# OLED_Shield.net
KiCad netlist of a schematic drawn in EAGLE
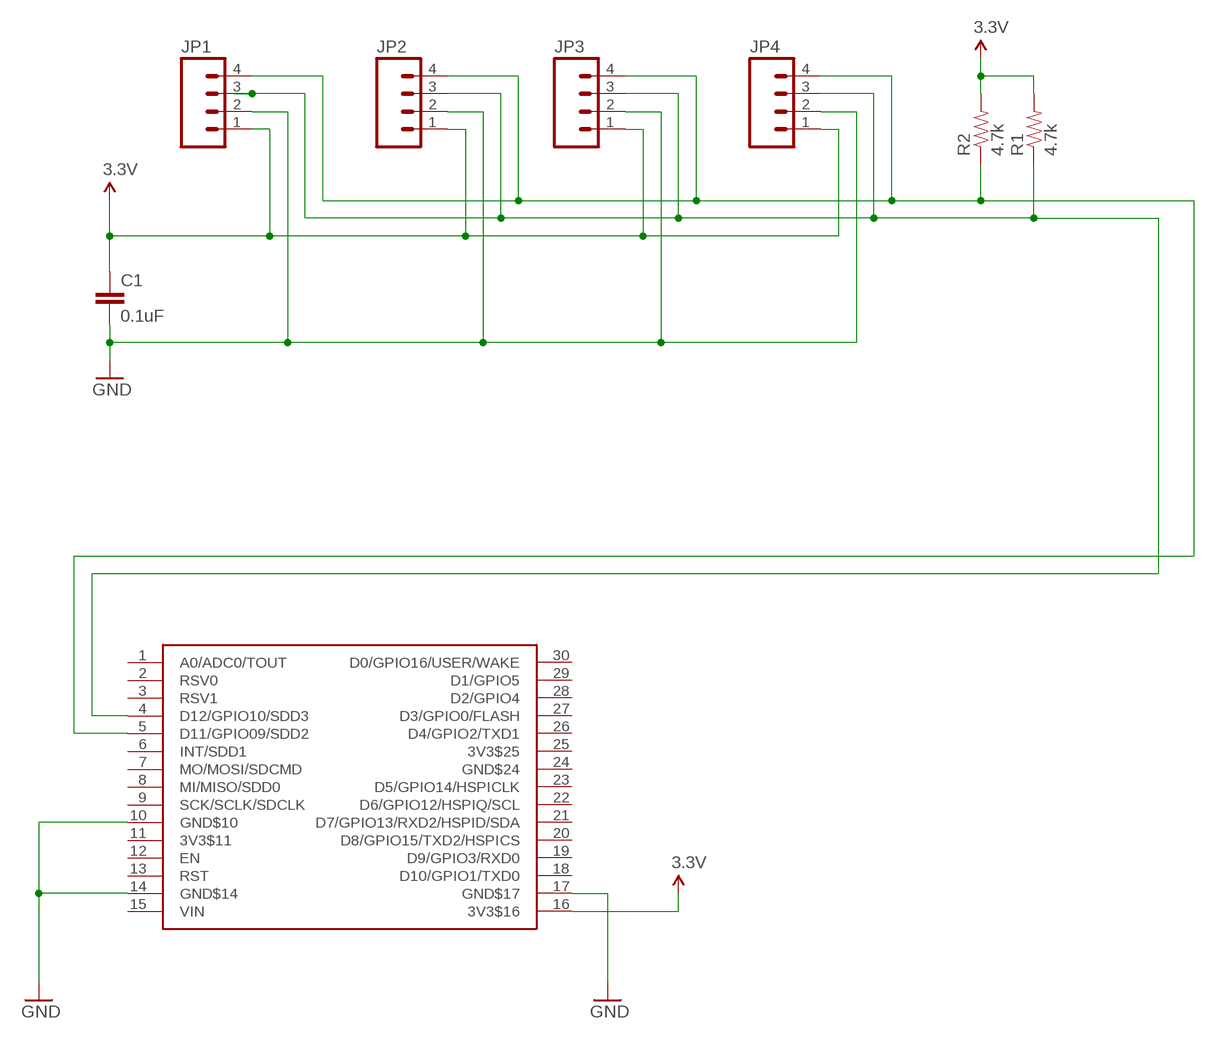
[diagram p0: schematic, sheet 1]

(export (version "E")
  (design (tool "Eeschema 10.0.6"))
  (components
    (comp (ref "C1")
      (value "0.1uF")
      (footprint "eagle-import:0402-CAP")
      (libsource (lib "eagle-import") (part "CAP0402-CAP"))
    )
    (comp (ref "JP1")
      (value "M041X04_NO_SILK")
      (footprint "eagle-import:1X04_NO_SILK")
      (libsource (lib "eagle-import") (part "M041X04_NO_SILK"))
    )
    (comp (ref "JP2")
      (value "M041X04_NO_SILK")
      (footprint "eagle-import:1X04_NO_SILK")
      (libsource (lib "eagle-import") (part "M041X04_NO_SILK"))
    )
    (comp (ref "JP3")
      (value "M041X04_NO_SILK")
      (footprint "eagle-import:1X04_NO_SILK")
      (libsource (lib "eagle-import") (part "M041X04_NO_SILK"))
    )
    (comp (ref "JP4")
      (value "M041X04_NO_SILK")
      (footprint "eagle-import:1X04_NO_SILK")
      (libsource (lib "eagle-import") (part "M041X04_NO_SILK"))
    )
    (comp (ref "R1")
      (value "4.7k")
      (footprint "eagle-import:0402-RES")
      (libsource (lib "eagle-import") (part "RESISTOR0402-RES"))
    )
    (comp (ref "R2")
      (value "4.7k")
      (footprint "eagle-import:0402-RES")
      (libsource (lib "eagle-import") (part "RESISTOR0402-RES"))
    )
    (comp (ref "U$1")
      (value "NERDSHIELD")
      (footprint "eagle-import:NERDUINO_STACK")
      (libsource (lib "eagle-import") (part "NERDSHIELD"))
    )
  )
  (nets
    (net (code "1") (name "3.3V") (class "Default")
      (node (ref "C1") (pin "1") (pinfunction "1_1") (pintype "passive"))
      (node (ref "JP1") (pin "1") (pinfunction "1_1") (pintype "passive"))
      (node (ref "JP2") (pin "1") (pinfunction "1_1") (pintype "passive"))
      (node (ref "JP3") (pin "1") (pinfunction "1_1") (pintype "passive"))
      (node (ref "JP4") (pin "1") (pinfunction "1_1") (pintype "passive"))
      (node (ref "R1") (pin "2") (pinfunction "2_2") (pintype "passive"))
      (node (ref "R2") (pin "2") (pinfunction "2_2") (pintype "passive"))
      (node (ref "U$1") (pin "16") (pinfunction "3V3$16_16") (pintype "bidirectional"))
    )
    (net (code "2") (name "GND") (class "Default")
      (node (ref "C1") (pin "2") (pinfunction "2_2") (pintype "passive"))
      (node (ref "JP1") (pin "2") (pinfunction "2_2") (pintype "passive"))
      (node (ref "JP2") (pin "2") (pinfunction "2_2") (pintype "passive"))
      (node (ref "JP3") (pin "2") (pinfunction "2_2") (pintype "passive"))
      (node (ref "JP4") (pin "2") (pinfunction "2_2") (pintype "passive"))
      (node (ref "U$1") (pin "10") (pinfunction "GND$10_10") (pintype "bidirectional"))
      (node (ref "U$1") (pin "14") (pinfunction "GND$14_14") (pintype "bidirectional"))
      (node (ref "U$1") (pin "17") (pinfunction "GND$17_17") (pintype "bidirectional"))
    )
    (net (code "3") (name "Net-(U$1-D11{slash}GPIO09{slash}SDD2)") (class "Default")
      (node (ref "JP1") (pin "4") (pinfunction "4_4") (pintype "passive"))
      (node (ref "JP2") (pin "4") (pinfunction "4_4") (pintype "passive"))
      (node (ref "JP3") (pin "4") (pinfunction "4_4") (pintype "passive"))
      (node (ref "JP4") (pin "4") (pinfunction "4_4") (pintype "passive"))
      (node (ref "R2") (pin "1") (pinfunction "1_1") (pintype "passive"))
      (node (ref "U$1") (pin "5") (pinfunction "D11/GPIO09/SDD2_5") (pintype "bidirectional"))
    )
    (net (code "4") (name "Net-(U$1-D12{slash}GPIO10{slash}SDD3)") (class "Default")
      (node (ref "JP1") (pin "3") (pinfunction "3_3") (pintype "passive"))
      (node (ref "JP2") (pin "3") (pinfunction "3_3") (pintype "passive"))
      (node (ref "JP3") (pin "3") (pinfunction "3_3") (pintype "passive"))
      (node (ref "JP4") (pin "3") (pinfunction "3_3") (pintype "passive"))
      (node (ref "R1") (pin "1") (pinfunction "1_1") (pintype "passive"))
      (node (ref "U$1") (pin "4") (pinfunction "D12/GPIO10/SDD3_4") (pintype "bidirectional"))
    )
    (net (code "5") (name "unconnected-(U$1-3V3$11-Pad11)") (class "Default")
      (node (ref "U$1") (pin "11") (pinfunction "3V3$11_11") (pintype "bidirectional"))
    )
    (net (code "6") (name "unconnected-(U$1-3V3$25-Pad25)") (class "Default")
      (node (ref "U$1") (pin "25") (pinfunction "3V3$25_25") (pintype "bidirectional"))
    )
    (net (code "7") (name "unconnected-(U$1-A0{slash}ADC0{slash}TOUT-Pad1)") (class "Default")
      (node (ref "U$1") (pin "1") (pinfunction "A0/ADC0/TOUT_1") (pintype "bidirectional"))
    )
    (net (code "8") (name "unconnected-(U$1-D0{slash}GPIO16{slash}USER{slash}WAKE-Pad30)") (class "Default")
      (node (ref "U$1") (pin "30") (pinfunction "D0/GPIO16/USER/WAKE_30") (pintype "bidirectional"))
    )
    (net (code "9") (name "unconnected-(U$1-D1{slash}GPIO5-Pad29)") (class "Default")
      (node (ref "U$1") (pin "29") (pinfunction "D1/GPIO5_29") (pintype "bidirectional"))
    )
    (net (code "10") (name "unconnected-(U$1-D2{slash}GPIO4-Pad28)") (class "Default")
      (node (ref "U$1") (pin "28") (pinfunction "D2/GPIO4_28") (pintype "bidirectional"))
    )
    (net (code "11") (name "unconnected-(U$1-D3{slash}GPIO0{slash}FLASH-Pad27)") (class "Default")
      (node (ref "U$1") (pin "27") (pinfunction "D3/GPIO0/FLASH_27") (pintype "bidirectional"))
    )
    (net (code "12") (name "unconnected-(U$1-D4{slash}GPIO2{slash}TXD1-Pad26)") (class "Default")
      (node (ref "U$1") (pin "26") (pinfunction "D4/GPIO2/TXD1_26") (pintype "bidirectional"))
    )
    (net (code "13") (name "unconnected-(U$1-D5{slash}GPIO14{slash}HSPICLK-Pad23)") (class "Default")
      (node (ref "U$1") (pin "23") (pinfunction "D5/GPIO14/HSPICLK_23") (pintype "bidirectional"))
    )
    (net (code "14") (name "unconnected-(U$1-D6{slash}GPIO12{slash}HSPIQ{slash}SCL-Pad22)") (class "Default")
      (node (ref "U$1") (pin "22") (pinfunction "D6/GPIO12/HSPIQ/SCL_22") (pintype "bidirectional"))
    )
    (net (code "15") (name "unconnected-(U$1-D7{slash}GPIO13{slash}RXD2{slash}HSPID{slash}SDA-Pad21)") (class "Default")
      (node (ref "U$1") (pin "21") (pinfunction "D7/GPIO13/RXD2/HSPID/SDA_21") (pintype "bidirectional"))
    )
    (net (code "16") (name "unconnected-(U$1-D8{slash}GPIO15{slash}TXD2{slash}HSPICS-Pad20)") (class "Default")
      (node (ref "U$1") (pin "20") (pinfunction "D8/GPIO15/TXD2/HSPICS_20") (pintype "bidirectional"))
    )
    (net (code "17") (name "unconnected-(U$1-D9{slash}GPIO3{slash}RXD0-Pad19)") (class "Default")
      (node (ref "U$1") (pin "19") (pinfunction "D9/GPIO3/RXD0_19") (pintype "bidirectional"))
    )
    (net (code "18") (name "unconnected-(U$1-D10{slash}GPIO1{slash}TXD0-Pad18)") (class "Default")
      (node (ref "U$1") (pin "18") (pinfunction "D10/GPIO1/TXD0_18") (pintype "bidirectional"))
    )
    (net (code "19") (name "unconnected-(U$1-EN-Pad12)") (class "Default")
      (node (ref "U$1") (pin "12") (pinfunction "EN_12") (pintype "bidirectional"))
    )
    (net (code "20") (name "unconnected-(U$1-GND$24-Pad24)") (class "Default")
      (node (ref "U$1") (pin "24") (pinfunction "GND$24_24") (pintype "bidirectional"))
    )
    (net (code "21") (name "unconnected-(U$1-INT{slash}SDD1-Pad6)") (class "Default")
      (node (ref "U$1") (pin "6") (pinfunction "INT/SDD1_6") (pintype "bidirectional"))
    )
    (net (code "22") (name "unconnected-(U$1-MI{slash}MISO{slash}SDD0-Pad8)") (class "Default")
      (node (ref "U$1") (pin "8") (pinfunction "MI/MISO/SDD0_8") (pintype "bidirectional"))
    )
    (net (code "23") (name "unconnected-(U$1-MO{slash}MOSI{slash}SDCMD-Pad7)") (class "Default")
      (node (ref "U$1") (pin "7") (pinfunction "MO/MOSI/SDCMD_7") (pintype "bidirectional"))
    )
    (net (code "24") (name "unconnected-(U$1-RST-Pad13)") (class "Default")
      (node (ref "U$1") (pin "13") (pinfunction "RST_13") (pintype "bidirectional"))
    )
    (net (code "25") (name "unconnected-(U$1-RSV0-Pad2)") (class "Default")
      (node (ref "U$1") (pin "2") (pinfunction "RSV0_2") (pintype "bidirectional"))
    )
    (net (code "26") (name "unconnected-(U$1-RSV1-Pad3)") (class "Default")
      (node (ref "U$1") (pin "3") (pinfunction "RSV1_3") (pintype "bidirectional"))
    )
    (net (code "27") (name "unconnected-(U$1-SCK{slash}SCLK{slash}SDCLK-Pad9)") (class "Default")
      (node (ref "U$1") (pin "9") (pinfunction "SCK/SCLK/SDCLK_9") (pintype "bidirectional"))
    )
    (net (code "28") (name "unconnected-(U$1-VIN-Pad15)") (class "Default")
      (node (ref "U$1") (pin "15") (pinfunction "VIN_15") (pintype "bidirectional"))
    )
  )
)
